# ESP32DevKitCv4_SA8x8_Ver_B.net
KiCad netlist of a schematic drawn in EAGLE
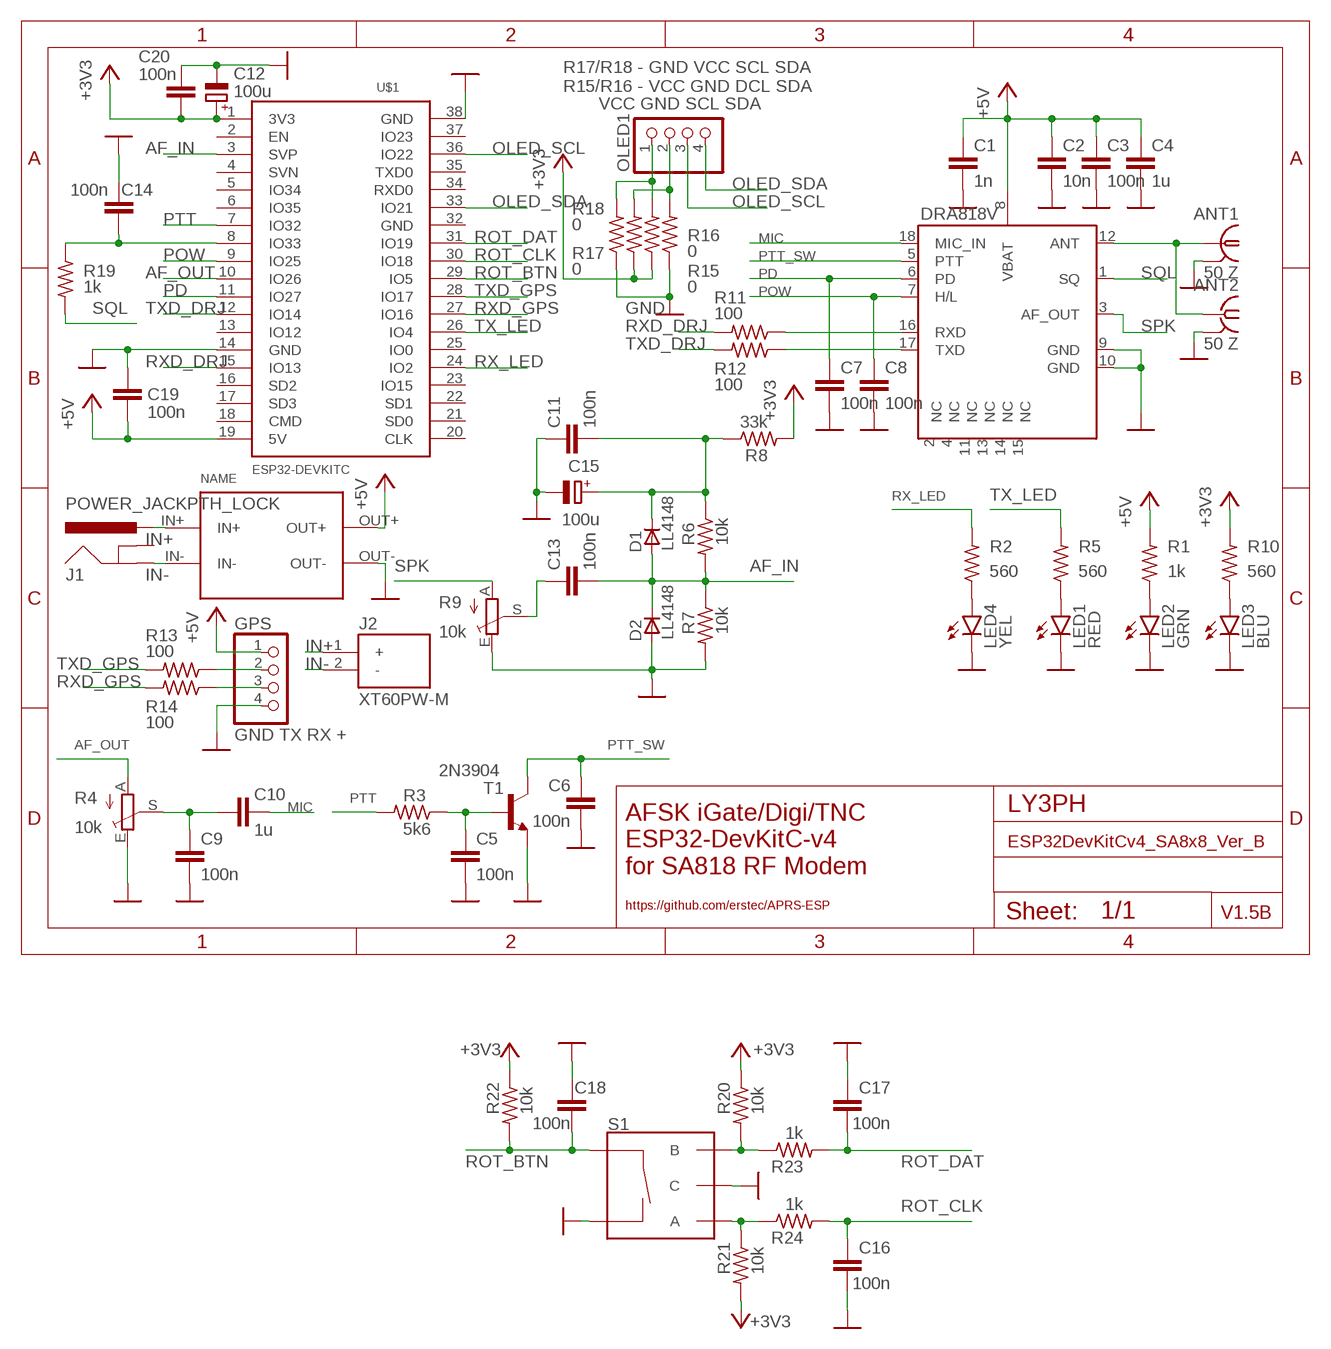
[diagram p0: schematic, sheet 1]

(export (version "E")
  (design (tool "Eeschema 10.0.6"))
  (components
    (comp (ref "ANT1")
      (value "50 Z")
      (footprint "eagle-import:LTI-SASF54GT")
      (libsource (lib "eagle-import") (part "LTI-SASF54GT"))
    )
    (comp (ref "ANT2")
      (value "50 Z")
      (footprint "eagle-import:J502-ND-142-0701-801_806")
      (fields (field (name "MF") "JOHNSON COMPONENTS") (field (name "MPN") "142-0701-801"))
      (libsource (lib "eagle-import") (part "SMA-142-0701-801/806"))
    )
    (comp (ref "C1")
      (value "1n")
      (footprint "eagle-import:C0805")
      (libsource (lib "eagle-import") (part "C-EUC0805"))
    )
    (comp (ref "C2")
      (value "10n")
      (footprint "eagle-import:C0805")
      (libsource (lib "eagle-import") (part "C-EUC0805"))
    )
    (comp (ref "C3")
      (value "100n")
      (footprint "eagle-import:C0805")
      (libsource (lib "eagle-import") (part "C-EUC0805"))
    )
    (comp (ref "C4")
      (value "1u")
      (footprint "eagle-import:C0805")
      (libsource (lib "eagle-import") (part "C-EUC0805"))
    )
    (comp (ref "C5")
      (value "100n")
      (footprint "eagle-import:C0805")
      (libsource (lib "eagle-import") (part "C-EUC0805"))
    )
    (comp (ref "C6")
      (value "100n")
      (footprint "eagle-import:C0805")
      (libsource (lib "eagle-import") (part "C-EUC0805"))
    )
    (comp (ref "C7")
      (value "100n")
      (footprint "eagle-import:C0805")
      (libsource (lib "eagle-import") (part "C-EUC0805"))
    )
    (comp (ref "C8")
      (value "100n")
      (footprint "eagle-import:C0805")
      (libsource (lib "eagle-import") (part "C-EUC0805"))
    )
    (comp (ref "C9")
      (value "100n")
      (footprint "eagle-import:C0805")
      (libsource (lib "eagle-import") (part "C-EUC0805"))
    )
    (comp (ref "C10")
      (value "1u")
      (footprint "eagle-import:C0805")
      (libsource (lib "eagle-import") (part "C-EUC0805"))
    )
    (comp (ref "C11")
      (value "100n")
      (footprint "eagle-import:C0805")
      (libsource (lib "eagle-import") (part "C-EUC0805"))
    )
    (comp (ref "C12")
      (value "100u")
      (footprint "eagle-import:SMC_D")
      (libsource (lib "eagle-import") (part "CPOL-EUSMCD"))
    )
    (comp (ref "C13")
      (value "100n")
      (footprint "eagle-import:C0805")
      (libsource (lib "eagle-import") (part "C-EUC0805"))
    )
    (comp (ref "C14")
      (value "100n")
      (footprint "eagle-import:C0805")
      (libsource (lib "eagle-import") (part "C-EUC0805"))
    )
    (comp (ref "C15")
      (value "100u")
      (footprint "eagle-import:SMC_D")
      (libsource (lib "eagle-import") (part "CPOL-EUSMCD"))
    )
    (comp (ref "C16")
      (value "100n")
      (footprint "eagle-import:C0805")
      (libsource (lib "eagle-import") (part "C-EUC0805"))
    )
    (comp (ref "C17")
      (value "100n")
      (footprint "eagle-import:C0805")
      (libsource (lib "eagle-import") (part "C-EUC0805"))
    )
    (comp (ref "C18")
      (value "100n")
      (footprint "eagle-import:C0805")
      (libsource (lib "eagle-import") (part "C-EUC0805"))
    )
    (comp (ref "C19")
      (value "100n")
      (footprint "eagle-import:C0805")
      (libsource (lib "eagle-import") (part "C-EUC0805"))
    )
    (comp (ref "C20")
      (value "100n")
      (footprint "eagle-import:C0805")
      (libsource (lib "eagle-import") (part "C-EUC0805"))
    )
    (comp (ref "D1")
      (value "LL4148")
      (footprint "eagle-import:SOD80_DO213AA_MINIMELF")
      (libsource (lib "eagle-import") (part "LL4148"))
    )
    (comp (ref "D2")
      (value "LL4148")
      (footprint "eagle-import:SOD80_DO213AA_MINIMELF")
      (libsource (lib "eagle-import") (part "LL4148"))
    )
    (comp (ref "DRA818V")
      (value "DRA818A")
      (footprint "eagle-import:DRA818A")
      (libsource (lib "eagle-import") (part "DRA818A"))
    )
    (comp (ref "GPS")
      (value "GND TX RX +")
      (footprint "eagle-import:1X04")
      (libsource (lib "eagle-import") (part "PINHD-1X4"))
    )
    (comp (ref "J1")
      (value "POWER_JACKPTH_LOCK")
      (footprint "eagle-import:POWER_JACK_PTH_LOCK")
      (libsource (lib "eagle-import") (part "POWER_JACKPTH_LOCK"))
    )
    (comp (ref "J2")
      (value "XT60PW-M")
      (footprint "eagle-import:AMASS_XT60PW-M")
      (fields (field (name "MF") "AMASS"))
      (libsource (lib "eagle-import") (part "XT60PW-M"))
    )
    (comp (ref "LED1")
      (value "RED")
      (footprint "eagle-import:CHIP-LED0805")
      (libsource (lib "eagle-import") (part "LEDCHIP-LED0805"))
    )
    (comp (ref "LED2")
      (value "GRN")
      (footprint "eagle-import:CHIP-LED0805")
      (libsource (lib "eagle-import") (part "LEDCHIP-LED0805"))
    )
    (comp (ref "LED3")
      (value "BLU")
      (footprint "eagle-import:CHIP-LED0805")
      (libsource (lib "eagle-import") (part "LEDCHIP-LED0805"))
    )
    (comp (ref "LED4")
      (value "YEL")
      (footprint "eagle-import:CHIP-LED0805")
      (libsource (lib "eagle-import") (part "LEDCHIP-LED0805"))
    )
    (comp (ref "OLED1")
      (value "VCC GND SCL SDA")
      (footprint "eagle-import:1X04")
      (libsource (lib "eagle-import") (part "PINHD-1X4"))
    )
    (comp (ref "R1")
      (value "1k")
      (footprint "eagle-import:R0805")
      (libsource (lib "eagle-import") (part "R-US_R0805"))
    )
    (comp (ref "R2")
      (value "560")
      (footprint "eagle-import:R0805")
      (libsource (lib "eagle-import") (part "R-US_R0805"))
    )
    (comp (ref "R3")
      (value "5k6")
      (footprint "eagle-import:R0805")
      (libsource (lib "eagle-import") (part "R-US_R0805"))
    )
    (comp (ref "R4")
      (value "10k")
      (footprint "eagle-import:CA6H")
      (libsource (lib "eagle-import") (part "TRIM_EU-CA6H"))
    )
    (comp (ref "R5")
      (value "560")
      (footprint "eagle-import:R0805")
      (libsource (lib "eagle-import") (part "R-US_R0805"))
    )
    (comp (ref "R6")
      (value "10k")
      (footprint "eagle-import:R0805")
      (libsource (lib "eagle-import") (part "R-US_R0805"))
    )
    (comp (ref "R7")
      (value "10k")
      (footprint "eagle-import:R0805")
      (libsource (lib "eagle-import") (part "R-US_R0805"))
    )
    (comp (ref "R8")
      (value "33k")
      (footprint "eagle-import:R0805")
      (libsource (lib "eagle-import") (part "R-US_R0805"))
    )
    (comp (ref "R9")
      (value "10k")
      (footprint "eagle-import:CA6H")
      (libsource (lib "eagle-import") (part "TRIM_EU-CA6H"))
    )
    (comp (ref "R10")
      (value "560")
      (footprint "eagle-import:R0805")
      (libsource (lib "eagle-import") (part "R-US_R0805"))
    )
    (comp (ref "R11")
      (value "100")
      (footprint "eagle-import:R0805")
      (libsource (lib "eagle-import") (part "R-US_R0805"))
    )
    (comp (ref "R12")
      (value "100")
      (footprint "eagle-import:R0805")
      (libsource (lib "eagle-import") (part "R-US_R0805"))
    )
    (comp (ref "R13")
      (value "100")
      (footprint "eagle-import:R0805")
      (libsource (lib "eagle-import") (part "R-US_R0805"))
    )
    (comp (ref "R14")
      (value "100")
      (footprint "eagle-import:R0805")
      (libsource (lib "eagle-import") (part "R-US_R0805"))
    )
    (comp (ref "R15")
      (value "0")
      (footprint "eagle-import:R0805")
      (libsource (lib "eagle-import") (part "R-US_R0805"))
    )
    (comp (ref "R16")
      (value "0")
      (footprint "eagle-import:R0805")
      (libsource (lib "eagle-import") (part "R-US_R0805"))
    )
    (comp (ref "R17")
      (value "0")
      (footprint "eagle-import:R0805")
      (libsource (lib "eagle-import") (part "R-US_R0805"))
    )
    (comp (ref "R18")
      (value "0")
      (footprint "eagle-import:R0805")
      (libsource (lib "eagle-import") (part "R-US_R0805"))
    )
    (comp (ref "R19")
      (value "1k")
      (footprint "eagle-import:R0805")
      (libsource (lib "eagle-import") (part "R-US_R0805"))
    )
    (comp (ref "R20")
      (value "10k")
      (footprint "eagle-import:R0805")
      (libsource (lib "eagle-import") (part "R-US_R0805"))
    )
    (comp (ref "R21")
      (value "10k")
      (footprint "eagle-import:R0805")
      (libsource (lib "eagle-import") (part "R-US_R0805"))
    )
    (comp (ref "R22")
      (value "10k")
      (footprint "eagle-import:R0805")
      (libsource (lib "eagle-import") (part "R-US_R0805"))
    )
    (comp (ref "R23")
      (value "1k")
      (footprint "eagle-import:R0805")
      (libsource (lib "eagle-import") (part "R-US_R0805"))
    )
    (comp (ref "R24")
      (value "1k")
      (footprint "eagle-import:R0805")
      (libsource (lib "eagle-import") (part "R-US_R0805"))
    )
    (comp (ref "S1")
      (value "ENCODER-SWITCH")
      (footprint "eagle-import:ROTARY_ENC_PLAIN")
      (libsource (lib "eagle-import") (part "ENCODER-SWITCH"))
    )
    (comp (ref "T1")
      (value "2N3904")
      (footprint "eagle-import:SOT23-BEC")
      (libsource (lib "eagle-import") (part "-NPN-SOT23-BECMMBT3904LT1"))
    )
    (comp (ref "U$1")
      (value "ESP32DEVKITC")
      (footprint "eagle-import:ESP32-DEVKITC")
      (libsource (lib "eagle-import") (part "ESP32DEVKITC"))
    )
    (comp (ref "U$2")
      (value "CP8-ADJ")
      (footprint "eagle-import:CP8-ADJ")
      (libsource (lib "eagle-import") (part "CP8-ADJ"))
    )
  )
  (nets
    (net (code "1") (name "+3V3") (class "Default")
      (node (ref "C12") (pin "+") (pinfunction "+_+") (pintype "passive"))
      (node (ref "C20") (pin "2") (pinfunction "2_2") (pintype "passive"))
      (node (ref "R10") (pin "2") (pinfunction "2_2") (pintype "passive"))
      (node (ref "R15") (pin "1") (pinfunction "1_1") (pintype "passive"))
      (node (ref "R17") (pin "1") (pinfunction "1_1") (pintype "passive"))
      (node (ref "R20") (pin "1") (pinfunction "1_1") (pintype "passive"))
      (node (ref "R21") (pin "2") (pinfunction "2_2") (pintype "passive"))
      (node (ref "R22") (pin "1") (pinfunction "1_1") (pintype "passive"))
      (node (ref "R8") (pin "2") (pinfunction "2_2") (pintype "passive"))
      (node (ref "U$1") (pin "1") (pinfunction "3V3_1") (pintype "bidirectional"))
    )
    (net (code "2") (name "+5V") (class "Default")
      (node (ref "C1") (pin "1") (pinfunction "1_1") (pintype "passive"))
      (node (ref "C19") (pin "2") (pinfunction "2_2") (pintype "passive"))
      (node (ref "C2") (pin "1") (pinfunction "1_1") (pintype "passive"))
      (node (ref "C3") (pin "1") (pinfunction "1_1") (pintype "passive"))
      (node (ref "C4") (pin "1") (pinfunction "1_1") (pintype "passive"))
      (node (ref "DRA818V") (pin "8") (pinfunction "VBAT_8") (pintype "bidirectional"))
      (node (ref "GPS") (pin "1") (pinfunction "1_1") (pintype "passive"))
      (node (ref "R1") (pin "2") (pinfunction "2_2") (pintype "passive"))
      (node (ref "U$1") (pin "19") (pinfunction "5V_19") (pintype "bidirectional"))
      (node (ref "U$2") (pin "OUT+") (pinfunction "OUT+_OUT+") (pintype "passive"))
    )
    (net (code "3") (name "/AF_IN") (class "Default")
      (node (ref "C13") (pin "2") (pinfunction "2_2") (pintype "passive"))
      (node (ref "D1") (pin "A") (pinfunction "A_A") (pintype "passive"))
      (node (ref "D2") (pin "C") (pinfunction "C_C") (pintype "passive"))
      (node (ref "R6") (pin "2") (pinfunction "2_2") (pintype "passive"))
      (node (ref "R7") (pin "1") (pinfunction "1_1") (pintype "passive"))
      (node (ref "U$1") (pin "3") (pinfunction "SVP_3") (pintype "bidirectional"))
    )
    (net (code "4") (name "/AF_OUT") (class "Default")
      (node (ref "R4") (pin "A") (pinfunction "A_A") (pintype "passive"))
      (node (ref "U$1") (pin "10") (pinfunction "IO26_10") (pintype "bidirectional"))
    )
    (net (code "5") (name "/IN+") (class "Default")
      (node (ref "J1") (pin "PWR") (pinfunction "PWR_PWR") (pintype "bidirectional"))
      (node (ref "J2") (pin "1") (pinfunction "+_1") (pintype "passive"))
      (node (ref "U$2") (pin "IN+") (pinfunction "IN+_IN+") (pintype "passive"))
    )
    (net (code "6") (name "/IN-") (class "Default")
      (node (ref "J1") (pin "GND") (pinfunction "GND_GND") (pintype "bidirectional"))
      (node (ref "J2") (pin "2") (pinfunction "-_2") (pintype "passive"))
      (node (ref "U$2") (pin "IN-") (pinfunction "IN-_IN-") (pintype "passive"))
    )
    (net (code "7") (name "/MIC") (class "Default")
      (node (ref "C10") (pin "2") (pinfunction "2_2") (pintype "passive"))
      (node (ref "DRA818V") (pin "18") (pinfunction "MIC_IN_18") (pintype "bidirectional"))
    )
    (net (code "8") (name "/OLED_SCL") (class "Default")
      (node (ref "OLED1") (pin "3") (pinfunction "3_3") (pintype "passive"))
      (node (ref "U$1") (pin "36") (pinfunction "IO22_36") (pintype "bidirectional"))
    )
    (net (code "9") (name "/OLED_SDA") (class "Default")
      (node (ref "OLED1") (pin "4") (pinfunction "4_4") (pintype "passive"))
      (node (ref "U$1") (pin "33") (pinfunction "IO21_33") (pintype "bidirectional"))
    )
    (net (code "10") (name "/PD") (class "Default")
      (node (ref "C7") (pin "1") (pinfunction "1_1") (pintype "passive"))
      (node (ref "DRA818V") (pin "6") (pinfunction "PD_6") (pintype "bidirectional"))
      (node (ref "U$1") (pin "11") (pinfunction "IO27_11") (pintype "bidirectional"))
    )
    (net (code "11") (name "/POW") (class "Default")
      (node (ref "C8") (pin "1") (pinfunction "1_1") (pintype "passive"))
      (node (ref "DRA818V") (pin "7") (pinfunction "H/L_7") (pintype "bidirectional"))
      (node (ref "U$1") (pin "9") (pinfunction "IO25_9") (pintype "bidirectional"))
    )
    (net (code "12") (name "/PTT") (class "Default")
      (node (ref "R3") (pin "2") (pinfunction "2_2") (pintype "passive"))
      (node (ref "U$1") (pin "7") (pinfunction "IO32_7") (pintype "bidirectional"))
    )
    (net (code "13") (name "/PTT_SW") (class "Default")
      (node (ref "C6") (pin "1") (pinfunction "1_1") (pintype "passive"))
      (node (ref "DRA818V") (pin "5") (pinfunction "PTT_5") (pintype "bidirectional"))
      (node (ref "T1") (pin "C") (pinfunction "C_C") (pintype "passive"))
    )
    (net (code "14") (name "/ROT_BTN") (class "Default")
      (node (ref "C18") (pin "2") (pinfunction "2_2") (pintype "passive"))
      (node (ref "R22") (pin "2") (pinfunction "2_2") (pintype "passive"))
      (node (ref "S1") (pin "SW+") (pinfunction "SW+_SW+") (pintype "bidirectional"))
      (node (ref "U$1") (pin "29") (pinfunction "IO5_29") (pintype "bidirectional"))
    )
    (net (code "15") (name "/ROT_CLK") (class "Default")
      (node (ref "C16") (pin "1") (pinfunction "1_1") (pintype "passive"))
      (node (ref "R24") (pin "2") (pinfunction "2_2") (pintype "passive"))
      (node (ref "U$1") (pin "30") (pinfunction "IO18_30") (pintype "bidirectional"))
    )
    (net (code "16") (name "/ROT_DAT") (class "Default")
      (node (ref "C17") (pin "2") (pinfunction "2_2") (pintype "passive"))
      (node (ref "R23") (pin "2") (pinfunction "2_2") (pintype "passive"))
      (node (ref "U$1") (pin "31") (pinfunction "IO19_31") (pintype "bidirectional"))
    )
    (net (code "17") (name "/RXD_DRJ") (class "Default")
      (node (ref "R11") (pin "2") (pinfunction "2_2") (pintype "passive"))
      (node (ref "U$1") (pin "15") (pinfunction "IO13_15") (pintype "bidirectional"))
    )
    (net (code "18") (name "/RXD_GPS") (class "Default")
      (node (ref "R14") (pin "2") (pinfunction "2_2") (pintype "passive"))
      (node (ref "U$1") (pin "27") (pinfunction "IO16_27") (pintype "bidirectional"))
    )
    (net (code "19") (name "/RX_LED") (class "Default")
      (node (ref "R2") (pin "2") (pinfunction "2_2") (pintype "passive"))
      (node (ref "U$1") (pin "24") (pinfunction "IO2_24") (pintype "bidirectional"))
    )
    (net (code "20") (name "/SPK") (class "Default")
      (node (ref "DRA818V") (pin "3") (pinfunction "AF_OUT_3") (pintype "bidirectional"))
      (node (ref "R9") (pin "A") (pinfunction "A_A") (pintype "passive"))
    )
    (net (code "21") (name "/SQL") (class "Default")
      (node (ref "DRA818V") (pin "1") (pinfunction "SQ_1") (pintype "bidirectional"))
      (node (ref "R19") (pin "2") (pinfunction "2_2") (pintype "passive"))
    )
    (net (code "22") (name "/TXD_DRJ") (class "Default")
      (node (ref "R12") (pin "2") (pinfunction "2_2") (pintype "passive"))
      (node (ref "U$1") (pin "12") (pinfunction "IO14_12") (pintype "bidirectional"))
    )
    (net (code "23") (name "/TXD_GPS") (class "Default")
      (node (ref "R13") (pin "2") (pinfunction "2_2") (pintype "passive"))
      (node (ref "U$1") (pin "28") (pinfunction "IO17_28") (pintype "bidirectional"))
    )
    (net (code "24") (name "/TX_LED") (class "Default")
      (node (ref "R5") (pin "2") (pinfunction "2_2") (pintype "passive"))
      (node (ref "U$1") (pin "26") (pinfunction "IO4_26") (pintype "bidirectional"))
    )
    (net (code "25") (name "GND") (class "Default")
      (node (ref "ANT1") (pin "2") (pinfunction "2_2") (pintype "passive"))
      (node (ref "ANT1") (pin "3") (pinfunction "2_3") (pintype "passive"))
      (node (ref "ANT1") (pin "4") (pinfunction "2_4") (pintype "passive"))
      (node (ref "ANT1") (pin "5") (pinfunction "2_5") (pintype "passive"))
      (node (ref "ANT2") (pin "G@1") (pinfunction "2_G@1") (pintype "passive"))
      (node (ref "ANT2") (pin "G@2") (pinfunction "2_G@2") (pintype "passive"))
      (node (ref "ANT2") (pin "G@3") (pinfunction "2_G@3") (pintype "passive"))
      (node (ref "ANT2") (pin "G@4") (pinfunction "2_G@4") (pintype "passive"))
      (node (ref "C1") (pin "2") (pinfunction "2_2") (pintype "passive"))
      (node (ref "C11") (pin "1") (pinfunction "1_1") (pintype "passive"))
      (node (ref "C12") (pin "-") (pinfunction "-_-") (pintype "passive"))
      (node (ref "C14") (pin "2") (pinfunction "2_2") (pintype "passive"))
      (node (ref "C15") (pin "-") (pinfunction "-_-") (pintype "passive"))
      (node (ref "C16") (pin "2") (pinfunction "2_2") (pintype "passive"))
      (node (ref "C17") (pin "1") (pinfunction "1_1") (pintype "passive"))
      (node (ref "C18") (pin "1") (pinfunction "1_1") (pintype "passive"))
      (node (ref "C19") (pin "1") (pinfunction "1_1") (pintype "passive"))
      (node (ref "C2") (pin "2") (pinfunction "2_2") (pintype "passive"))
      (node (ref "C20") (pin "1") (pinfunction "1_1") (pintype "passive"))
      (node (ref "C3") (pin "2") (pinfunction "2_2") (pintype "passive"))
      (node (ref "C4") (pin "2") (pinfunction "2_2") (pintype "passive"))
      (node (ref "C5") (pin "2") (pinfunction "2_2") (pintype "passive"))
      (node (ref "C6") (pin "2") (pinfunction "2_2") (pintype "passive"))
      (node (ref "C7") (pin "2") (pinfunction "2_2") (pintype "passive"))
      (node (ref "C8") (pin "2") (pinfunction "2_2") (pintype "passive"))
      (node (ref "C9") (pin "2") (pinfunction "2_2") (pintype "passive"))
      (node (ref "D2") (pin "A") (pinfunction "A_A") (pintype "passive"))
      (node (ref "DRA818V") (pin "10") (pinfunction "GND_10") (pintype "bidirectional"))
      (node (ref "DRA818V") (pin "9") (pinfunction "GND_9") (pintype "bidirectional"))
      (node (ref "GPS") (pin "4") (pinfunction "4_4") (pintype "passive"))
      (node (ref "LED1") (pin "C") (pinfunction "C_C") (pintype "passive"))
      (node (ref "LED2") (pin "C") (pinfunction "C_C") (pintype "passive"))
      (node (ref "LED3") (pin "C") (pinfunction "C_C") (pintype "passive"))
      (node (ref "LED4") (pin "C") (pinfunction "C_C") (pintype "passive"))
      (node (ref "R16") (pin "1") (pinfunction "1_1") (pintype "passive"))
      (node (ref "R18") (pin "1") (pinfunction "1_1") (pintype "passive"))
      (node (ref "R4") (pin "E") (pinfunction "E_E") (pintype "passive"))
      (node (ref "R7") (pin "2") (pinfunction "2_2") (pintype "passive"))
      (node (ref "R9") (pin "E") (pinfunction "E_E") (pintype "passive"))
      (node (ref "S1") (pin "C") (pinfunction "C_C") (pintype "bidirectional"))
      (node (ref "S1") (pin "SW-") (pinfunction "SW-_SW-") (pintype "bidirectional"))
      (node (ref "T1") (pin "E") (pinfunction "E_E") (pintype "passive"))
      (node (ref "U$1") (pin "14") (pinfunction "GND_14") (pintype "bidirectional"))
      (node (ref "U$1") (pin "38") (pinfunction "GND_38") (pintype "bidirectional"))
      (node (ref "U$2") (pin "OUT-") (pinfunction "OUT-_OUT-") (pintype "passive"))
    )
    (net (code "26") (name "Net-(C5-Pad1)") (class "Default")
      (node (ref "C5") (pin "1") (pinfunction "1_1") (pintype "passive"))
      (node (ref "R3") (pin "1") (pinfunction "1_1") (pintype "passive"))
      (node (ref "T1") (pin "B") (pinfunction "B_B") (pintype "passive"))
    )
    (net (code "27") (name "Net-(C10-Pad1)") (class "Default")
      (node (ref "C10") (pin "1") (pinfunction "1_1") (pintype "passive"))
      (node (ref "C9") (pin "1") (pinfunction "1_1") (pintype "passive"))
      (node (ref "R4") (pin "S") (pinfunction "S_S") (pintype "passive"))
    )
    (net (code "28") (name "Net-(C11-Pad2)") (class "Default")
      (node (ref "C11") (pin "2") (pinfunction "2_2") (pintype "passive"))
      (node (ref "C15") (pin "+") (pinfunction "+_+") (pintype "passive"))
      (node (ref "D1") (pin "C") (pinfunction "C_C") (pintype "passive"))
      (node (ref "R6") (pin "1") (pinfunction "1_1") (pintype "passive"))
      (node (ref "R8") (pin "1") (pinfunction "1_1") (pintype "passive"))
    )
    (net (code "29") (name "Net-(C13-Pad1)") (class "Default")
      (node (ref "C13") (pin "1") (pinfunction "1_1") (pintype "passive"))
      (node (ref "R9") (pin "S") (pinfunction "S_S") (pintype "passive"))
    )
    (net (code "30") (name "Net-(DRA818V-ANT)") (class "Default")
      (node (ref "ANT1") (pin "1") (pinfunction "1_1") (pintype "passive"))
      (node (ref "ANT2") (pin "1") (pinfunction "1_1") (pintype "passive"))
      (node (ref "DRA818V") (pin "12") (pinfunction "ANT_12") (pintype "bidirectional"))
    )
    (net (code "31") (name "Net-(DRA818V-RXD)") (class "Default")
      (node (ref "DRA818V") (pin "16") (pinfunction "RXD_16") (pintype "bidirectional"))
      (node (ref "R11") (pin "1") (pinfunction "1_1") (pintype "passive"))
    )
    (net (code "32") (name "Net-(DRA818V-TXD)") (class "Default")
      (node (ref "DRA818V") (pin "17") (pinfunction "TXD_17") (pintype "bidirectional"))
      (node (ref "R12") (pin "1") (pinfunction "1_1") (pintype "passive"))
    )
    (net (code "33") (name "Net-(GPS-Pad2)") (class "Default")
      (node (ref "GPS") (pin "2") (pinfunction "2_2") (pintype "passive"))
      (node (ref "R13") (pin "1") (pinfunction "1_1") (pintype "passive"))
    )
    (net (code "34") (name "Net-(GPS-Pad3)") (class "Default")
      (node (ref "GPS") (pin "3") (pinfunction "3_3") (pintype "passive"))
      (node (ref "R14") (pin "1") (pinfunction "1_1") (pintype "passive"))
    )
    (net (code "35") (name "Net-(LED1-PadA)") (class "Default")
      (node (ref "LED1") (pin "A") (pinfunction "A_A") (pintype "passive"))
      (node (ref "R5") (pin "1") (pinfunction "1_1") (pintype "passive"))
    )
    (net (code "36") (name "Net-(LED2-PadA)") (class "Default")
      (node (ref "LED2") (pin "A") (pinfunction "A_A") (pintype "passive"))
      (node (ref "R1") (pin "1") (pinfunction "1_1") (pintype "passive"))
    )
    (net (code "37") (name "Net-(LED3-PadA)") (class "Default")
      (node (ref "LED3") (pin "A") (pinfunction "A_A") (pintype "passive"))
      (node (ref "R10") (pin "1") (pinfunction "1_1") (pintype "passive"))
    )
    (net (code "38") (name "Net-(LED4-PadA)") (class "Default")
      (node (ref "LED4") (pin "A") (pinfunction "A_A") (pintype "passive"))
      (node (ref "R2") (pin "1") (pinfunction "1_1") (pintype "passive"))
    )
    (net (code "39") (name "Net-(OLED1-Pad1)") (class "Default")
      (node (ref "OLED1") (pin "1") (pinfunction "1_1") (pintype "passive"))
      (node (ref "R15") (pin "2") (pinfunction "2_2") (pintype "passive"))
      (node (ref "R18") (pin "2") (pinfunction "2_2") (pintype "passive"))
    )
    (net (code "40") (name "Net-(OLED1-Pad2)") (class "Default")
      (node (ref "OLED1") (pin "2") (pinfunction "2_2") (pintype "passive"))
      (node (ref "R16") (pin "2") (pinfunction "2_2") (pintype "passive"))
      (node (ref "R17") (pin "2") (pinfunction "2_2") (pintype "passive"))
    )
    (net (code "41") (name "Net-(R20-Pad2)") (class "Default")
      (node (ref "R20") (pin "2") (pinfunction "2_2") (pintype "passive"))
      (node (ref "R23") (pin "1") (pinfunction "1_1") (pintype "passive"))
      (node (ref "S1") (pin "B") (pinfunction "B_B") (pintype "bidirectional"))
    )
    (net (code "42") (name "Net-(R21-Pad1)") (class "Default")
      (node (ref "R21") (pin "1") (pinfunction "1_1") (pintype "passive"))
      (node (ref "R24") (pin "1") (pinfunction "1_1") (pintype "passive"))
      (node (ref "S1") (pin "A") (pinfunction "A_A") (pintype "bidirectional"))
    )
    (net (code "43") (name "Net-(U$1-IO33)") (class "Default")
      (node (ref "C14") (pin "1") (pinfunction "1_1") (pintype "passive"))
      (node (ref "R19") (pin "1") (pinfunction "1_1") (pintype "passive"))
      (node (ref "U$1") (pin "8") (pinfunction "IO33_8") (pintype "bidirectional"))
    )
    (net (code "44") (name "unconnected-(DRA818V-NC-Pad2)") (class "Default")
      (node (ref "DRA818V") (pin "2") (pinfunction "NC_2") (pintype "bidirectional"))
    )
    (net (code "45") (name "unconnected-(DRA818V-NC-Pad4)") (class "Default")
      (node (ref "DRA818V") (pin "4") (pinfunction "NC_4") (pintype "bidirectional"))
    )
    (net (code "46") (name "unconnected-(DRA818V-NC-Pad11)") (class "Default")
      (node (ref "DRA818V") (pin "11") (pinfunction "NC_11") (pintype "bidirectional"))
    )
    (net (code "47") (name "unconnected-(DRA818V-NC-Pad13)") (class "Default")
      (node (ref "DRA818V") (pin "13") (pinfunction "NC_13") (pintype "bidirectional"))
    )
    (net (code "48") (name "unconnected-(DRA818V-NC-Pad14)") (class "Default")
      (node (ref "DRA818V") (pin "14") (pinfunction "NC_14") (pintype "bidirectional"))
    )
    (net (code "49") (name "unconnected-(DRA818V-NC-Pad15)") (class "Default")
      (node (ref "DRA818V") (pin "15") (pinfunction "NC_15") (pintype "bidirectional"))
    )
    (net (code "50") (name "unconnected-(J1-PadGNDBREAK)") (class "Default")
      (node (ref "J1") (pin "GNDBREAK") (pinfunction "GNDBREAK_GNDBREAK") (pintype "bidirectional"))
    )
    (net (code "51") (name "unconnected-(U$1-CLK-Pad20)") (class "Default")
      (node (ref "U$1") (pin "20") (pinfunction "CLK_20") (pintype "bidirectional"))
    )
    (net (code "52") (name "unconnected-(U$1-CMD-Pad18)") (class "Default")
      (node (ref "U$1") (pin "18") (pinfunction "CMD_18") (pintype "bidirectional"))
    )
    (net (code "53") (name "unconnected-(U$1-EN-Pad2)") (class "Default")
      (node (ref "U$1") (pin "2") (pinfunction "EN_2") (pintype "bidirectional"))
    )
    (net (code "54") (name "unconnected-(U$1-GND-Pad32)") (class "Default")
      (node (ref "U$1") (pin "32") (pinfunction "GND_32") (pintype "bidirectional"))
    )
    (net (code "55") (name "unconnected-(U$1-IO0-Pad25)") (class "Default")
      (node (ref "U$1") (pin "25") (pinfunction "IO0_25") (pintype "bidirectional"))
    )
    (net (code "56") (name "unconnected-(U$1-IO12-Pad13)") (class "Default")
      (node (ref "U$1") (pin "13") (pinfunction "IO12_13") (pintype "bidirectional"))
    )
    (net (code "57") (name "unconnected-(U$1-IO15-Pad23)") (class "Default")
      (node (ref "U$1") (pin "23") (pinfunction "IO15_23") (pintype "bidirectional"))
    )
    (net (code "58") (name "unconnected-(U$1-IO23-Pad37)") (class "Default")
      (node (ref "U$1") (pin "37") (pinfunction "IO23_37") (pintype "bidirectional"))
    )
    (net (code "59") (name "unconnected-(U$1-IO34-Pad5)") (class "Default")
      (node (ref "U$1") (pin "5") (pinfunction "IO34_5") (pintype "bidirectional"))
    )
    (net (code "60") (name "unconnected-(U$1-IO35-Pad6)") (class "Default")
      (node (ref "U$1") (pin "6") (pinfunction "IO35_6") (pintype "bidirectional"))
    )
    (net (code "61") (name "unconnected-(U$1-RXD0-Pad34)") (class "Default")
      (node (ref "U$1") (pin "34") (pinfunction "RXD0_34") (pintype "bidirectional"))
    )
    (net (code "62") (name "unconnected-(U$1-SD0-Pad21)") (class "Default")
      (node (ref "U$1") (pin "21") (pinfunction "SD0_21") (pintype "bidirectional"))
    )
    (net (code "63") (name "unconnected-(U$1-SD1-Pad22)") (class "Default")
      (node (ref "U$1") (pin "22") (pinfunction "SD1_22") (pintype "bidirectional"))
    )
    (net (code "64") (name "unconnected-(U$1-SD2-Pad16)") (class "Default")
      (node (ref "U$1") (pin "16") (pinfunction "SD2_16") (pintype "bidirectional"))
    )
    (net (code "65") (name "unconnected-(U$1-SD3-Pad17)") (class "Default")
      (node (ref "U$1") (pin "17") (pinfunction "SD3_17") (pintype "bidirectional"))
    )
    (net (code "66") (name "unconnected-(U$1-SVN-Pad4)") (class "Default")
      (node (ref "U$1") (pin "4") (pinfunction "SVN_4") (pintype "bidirectional"))
    )
    (net (code "67") (name "unconnected-(U$1-TXD0-Pad35)") (class "Default")
      (node (ref "U$1") (pin "35") (pinfunction "TXD0_35") (pintype "bidirectional"))
    )
  )
)
